# high_pass.net
KiCad netlist of a schematic drawn in Altium Designer
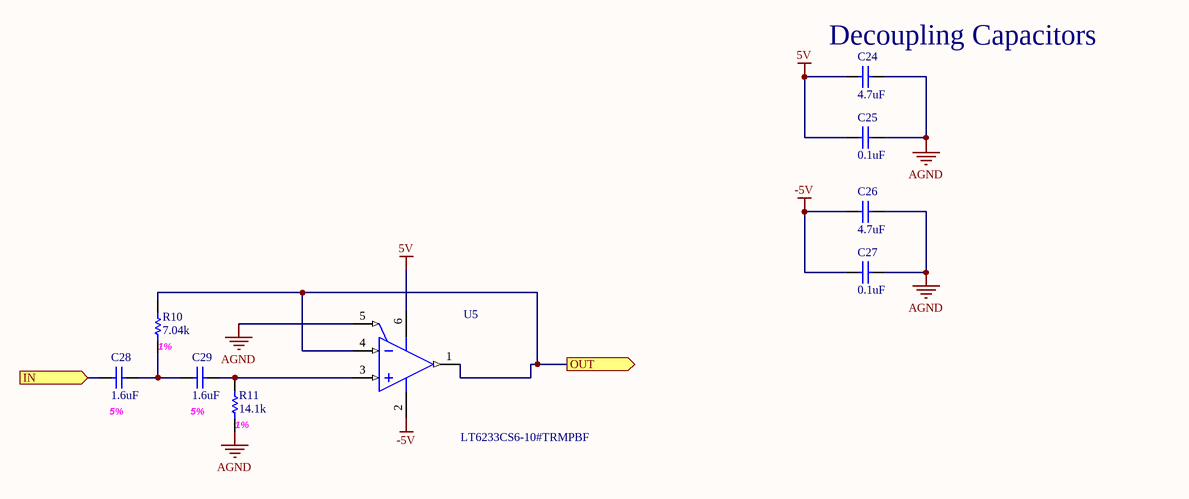
[diagram p0: high_pass.SchDoc]

(export (version "E")
  (design (tool "Eeschema 10.0.6"))
  (components
    (comp (ref "C24")
      (value "4.7uF")
      (footprint "0402_Cap")
      (description "Capacitor, 4.7uF, 0805")
      (libsource (lib "Arturo_Approved") (part "CL21A475KAQNNNE"))
    )
    (comp (ref "C25")
      (value "0.1uF")
      (footprint "0402_Cap")
      (description "Capacitor, 0.1uF, 0805")
      (libsource (lib "Arturo_Approved") (part "CL21B104KACNNNC"))
    )
    (comp (ref "C26")
      (value "4.7uF")
      (footprint "0402_Cap")
      (description "Capacitor, 4.7uF, 0805")
      (libsource (lib "Arturo_Approved") (part "CL21A475KAQNNNE"))
    )
    (comp (ref "C27")
      (value "0.1uF")
      (footprint "0402_Cap")
      (description "Capacitor, 0.1uF, 0805")
      (libsource (lib "Arturo_Approved") (part "CL21B104KACNNNC"))
    )
    (comp (ref "C28")
      (value "1.6uF")
      (footprint "0402_Cap")
      (description "Capacitor, 560nF, 0805, 25V")
      (libsource (lib "Arturo_Approved") (part "GRM219R71C564KA01D"))
    )
    (comp (ref "C29")
      (value "1.6uF")
      (footprint "0402_Cap")
      (description "Capacitor, 560nF, 0805, 25V")
      (libsource (lib "Arturo_Approved") (part "GRM219R71C564KA01D"))
    )
    (comp (ref "R10")
      (value "7.04k")
      (footprint "0402_Res")
      (description "7.5K 1% 1/4W")
      (libsource (lib "Arturo_Approved") (part "ERJ-PB6D7501V"))
    )
    (comp (ref "R11")
      (value "14.1k")
      (footprint "0402_Res")
      (description "14.7K 1% 1/4W")
      (libsource (lib "Arturo_Approved") (part "RC0805FR-0714K7L"))
    )
    (comp (ref "U5")
      (value "LT6233CS6-10#TRMPBF")
      (footprint "LT-S6-6-TSOT-23_N")
      (fields
        (field (name "LINEAR TECHNOLOGY PART NUMBER") "LT6233")
        (field (name "MANUFACTURER") "Linear Technology")
      )
      (libsource (lib "Altium Content Vault") (part "LT-LT623X-6"))
    )
  )
  (nets
    (net (code "1") (name "-5V") (class "Default")
      (node (ref "C26") (pin "1") (pinfunction "1_1") (pintype "passive"))
      (node (ref "C27") (pin "1") (pinfunction "1_1") (pintype "passive"))
      (node (ref "U5") (pin "2") (pinfunction "V-_2") (pintype "power_in"))
    )
    (net (code "2") (name "/IN") (class "Default")
      (node (ref "C28") (pin "1") (pinfunction "1_1") (pintype "passive"))
    )
    (net (code "3") (name "/OUT") (class "Default")
      (node (ref "R10") (pin "2") (pinfunction "2_2") (pintype "passive"))
      (node (ref "U5") (pin "1") (pinfunction "OUT_1") (pintype "output"))
      (node (ref "U5") (pin "4") (pinfunction "-IN_4") (pintype "input"))
    )
    (net (code "4") (name "5V") (class "Default")
      (node (ref "C24") (pin "1") (pinfunction "1_1") (pintype "passive"))
      (node (ref "C25") (pin "1") (pinfunction "1_1") (pintype "passive"))
      (node (ref "U5") (pin "6") (pinfunction "V+_6") (pintype "power_in"))
    )
    (net (code "5") (name "AGND") (class "Default")
      (node (ref "C24") (pin "2") (pinfunction "2_2") (pintype "passive"))
      (node (ref "C25") (pin "2") (pinfunction "2_2") (pintype "passive"))
      (node (ref "C26") (pin "2") (pinfunction "2_2") (pintype "passive"))
      (node (ref "C27") (pin "2") (pinfunction "2_2") (pintype "passive"))
      (node (ref "R11") (pin "1") (pinfunction "1_1") (pintype "passive"))
      (node (ref "U5") (pin "5") (pinfunction "~{ENABLE}_5") (pintype "input"))
    )
    (net (code "6") (name "Net-(C28-Pad2)") (class "Default")
      (node (ref "C28") (pin "2") (pinfunction "2_2") (pintype "passive"))
      (node (ref "C29") (pin "1") (pinfunction "1_1") (pintype "passive"))
      (node (ref "R10") (pin "1") (pinfunction "1_1") (pintype "passive"))
    )
    (net (code "7") (name "Net-(U5-+IN)") (class "Default")
      (node (ref "C29") (pin "2") (pinfunction "2_2") (pintype "passive"))
      (node (ref "R11") (pin "2") (pinfunction "2_2") (pintype "passive"))
      (node (ref "U5") (pin "3") (pinfunction "+IN_3") (pintype "input"))
    )
  )
)
